# Sch_MCU.net
KiCad netlist of a schematic drawn in Altium Designer
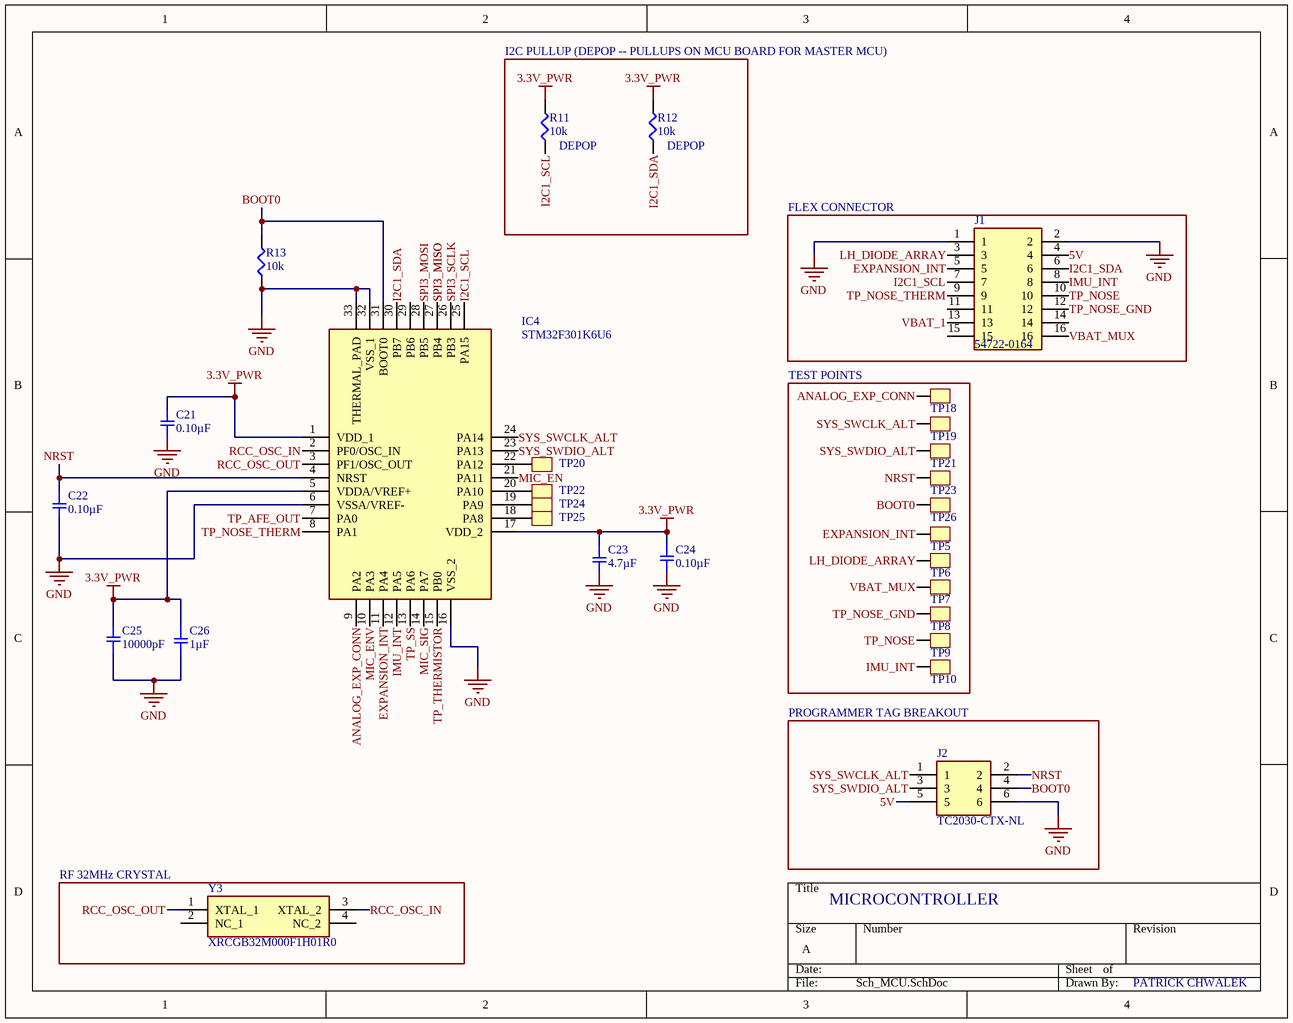
[diagram p0: Sch_MCU.SchDoc]

(export (version "E")
  (design (tool "Eeschema 10.0.6"))
  (components
    (comp (ref "C21")
      (value "0.10µF")
      (footprint "SMD-0402C")
      (description "CAP CER 0.1UF 16V X7R 0402")
      (fields
        (field (name "DIGI-KEY PART NUMBER") "490-4759-1-ND")
        (field (name "PART NUMBER") "GCM155R71C104KA55D")
      )
      (libsource (lib "capacitor_murata_0402") (part "GCM155R71C104KA55D"))
    )
    (comp (ref "C22")
      (value "0.10µF")
      (footprint "SMD-0402C")
      (description "CAP CER 0.1UF 16V X7R 0402")
      (fields
        (field (name "DIGI-KEY PART NUMBER") "490-4759-1-ND")
        (field (name "PART NUMBER") "GCM155R71C104KA55D")
      )
      (libsource (lib "capacitor_murata_0402") (part "GCM155R71C104KA55D"))
    )
    (comp (ref "C23")
      (value "4.7µF")
      (footprint "SMD-0402C")
      (description "CAP CER 4.7UF 4V X5R 0402")
      (fields
        (field (name "DIGI-KEY PART NUMBER") "490-13231-1-ND")
        (field (name "PART NUMBER") "GRM153R60G475ME15D")
      )
      (libsource (lib "capacitor_murata_0402") (part "GRM153R60G475ME15D"))
    )
    (comp (ref "C24")
      (value "0.10µF")
      (footprint "SMD-0402C")
      (description "CAP CER 0.1UF 16V X7R 0402")
      (fields
        (field (name "DIGI-KEY PART NUMBER") "490-4759-1-ND")
        (field (name "PART NUMBER") "GCM155R71C104KA55D")
      )
      (libsource (lib "capacitor_murata_0402") (part "GCM155R71C104KA55D"))
    )
    (comp (ref "C25")
      (value "10000pF")
      (footprint "SMD-0402C")
      (description "CAP CER 10000PF 50V X7R 0402")
      (fields
        (field (name "DIGI-KEY PART NUMBER") "490-4762-1-ND")
        (field (name "PART NUMBER") "GCM155R71H103KA55D")
      )
      (libsource (lib "capacitor_murata_0402") (part "GCM155R71H103KA55D"))
    )
    (comp (ref "C26")
      (value "1µF")
      (footprint "SMD-0402C")
      (description "CAP CER 1UF 10V X7S 0402")
      (fields
        (field (name "DIGI-KEY PART NUMBER") "490-13409-1-ND")
        (field (name "PART NUMBER") "GCM155C71A105KE38D")
      )
      (libsource (lib "capacitor_murata_0402") (part "GCM155C71A105KE38D"))
    )
    (comp (ref "IC4")
      (value "STM32F301K6U6")
      (footprint "SamacSys:QFN50P500X500X60-33N-D")
      (description "Integrated Circuit")
      (fields (field (name "MOUSER PART NUMBER") "511-STM32F301K6U6"))
      (libsource (lib "*") (part "STM32F301K6U6"))
    )
    (comp (ref "J1")
      (value "54722-0164")
      (footprint "SamacSys:54722-0164")
      (description "Connector")
      (fields (field (name "MOUSER PART NUMBER") "538-54722-0164") (field (name "RS PART NUMBER") "7206511"))
      (libsource (lib "*") (part "54722-0164"))
    )
    (comp (ref "J2")
      (value "TC2030-CTX-NL")
      (footprint "SamacSys:TC2030MCPNL10")
      (description "Connector")
      (libsource (lib "SamacSys") (part "TC2030-CTX-NL"))
    )
    (comp (ref "R11")
      (value "10k")
      (footprint "SMD-0402-RES")
      (description "RES SMD 10K OHM 5% 1/10W 0402")
      (fields (field (name "PART NUMBER") "ERJ-2GEJ103X") (field (name "DIGI-KEY PART NUMBER") "P10KJCT-ND"))
      (libsource (lib "Panasonic_ERJ_0402") (part "ERJ-2GEJ103X"))
    )
    (comp (ref "R12")
      (value "10k")
      (footprint "SMD-0402-RES")
      (description "RES SMD 10K OHM 5% 1/10W 0402")
      (fields (field (name "PART NUMBER") "ERJ-2GEJ103X") (field (name "DIGI-KEY PART NUMBER") "P10KJCT-ND"))
      (libsource (lib "Panasonic_ERJ_0402") (part "ERJ-2GEJ103X"))
    )
    (comp (ref "R13")
      (value "10k")
      (footprint "SMD-0402-RES")
      (description "RES SMD 10K OHM 5% 1/10W 0402")
      (fields (field (name "PART NUMBER") "ERJ-2GEJ103X") (field (name "DIGI-KEY PART NUMBER") "P10KJCT-ND"))
      (libsource (lib "Panasonic_ERJ_0402") (part "ERJ-2GEJ103X"))
    )
    (comp (ref "TP5")
      (value "TestPoint")
      (footprint "TestPoint_0.4mm")
      (libsource (lib "schematic_components") (part "TestPoint"))
    )
    (comp (ref "TP6")
      (value "TestPoint")
      (footprint "TestPoint_0.4mm")
      (libsource (lib "schematic_components") (part "TestPoint"))
    )
    (comp (ref "TP7")
      (value "TestPoint")
      (footprint "TestPoint_0.4mm")
      (libsource (lib "schematic_components") (part "TestPoint"))
    )
    (comp (ref "TP8")
      (value "TestPoint")
      (footprint "TestPoint_0.4mm")
      (libsource (lib "schematic_components") (part "TestPoint"))
    )
    (comp (ref "TP9")
      (value "TestPoint")
      (footprint "TestPoint_0.4mm")
      (libsource (lib "schematic_components") (part "TestPoint"))
    )
    (comp (ref "TP10")
      (value "TestPoint")
      (footprint "TestPoint_0.4mm")
      (libsource (lib "schematic_components") (part "TestPoint"))
    )
    (comp (ref "TP18")
      (value "TestPoint")
      (footprint "TestPoint_0.4mm")
      (libsource (lib "schematic_components") (part "TestPoint"))
    )
    (comp (ref "TP19")
      (value "TestPoint")
      (footprint "TestPoint_0.4mm")
      (libsource (lib "schematic_components") (part "TestPoint"))
    )
    (comp (ref "TP20")
      (value "TestPoint")
      (footprint "TESTPOINT_1MM_OVAL")
      (libsource (lib "schematic_components") (part "TestPoint"))
    )
    (comp (ref "TP21")
      (value "TestPoint")
      (footprint "TestPoint_0.4mm")
      (libsource (lib "schematic_components") (part "TestPoint"))
    )
    (comp (ref "TP22")
      (value "TestPoint")
      (footprint "TESTPOINT_1MM_OVAL")
      (libsource (lib "schematic_components") (part "TestPoint"))
    )
    (comp (ref "TP23")
      (value "TestPoint")
      (footprint "TestPoint_0.4mm")
      (libsource (lib "schematic_components") (part "TestPoint"))
    )
    (comp (ref "TP24")
      (value "TestPoint")
      (footprint "TESTPOINT_1MM_OVAL")
      (libsource (lib "schematic_components") (part "TestPoint"))
    )
    (comp (ref "TP25")
      (value "TestPoint")
      (footprint "TESTPOINT_1MM_OVAL")
      (libsource (lib "schematic_components") (part "TestPoint"))
    )
    (comp (ref "TP26")
      (value "TestPoint")
      (footprint "TestPoint_0.4mm")
      (libsource (lib "schematic_components") (part "TestPoint"))
    )
    (comp (ref "Y3")
      (value "XRCGB32M000F1H01R0")
      (footprint "SamacSys:XRCGB32M000F1H01R0")
      (description "Crystal or Oscillator")
      (fields (field (name "MOUSER PART NUMBER") "81-XRCGB32M000F1H01R"))
      (libsource (lib "SamacSys") (part "XRCGB32M000F1H01R0"))
    )
  )
  (nets
    (net (code "1") (name "/5V") (class "Default")
      (node (ref "J1") (pin "4") (pinfunction "4_4") (pintype "passive"))
      (node (ref "J2") (pin "5") (pinfunction "5_5") (pintype "passive"))
    )
    (net (code "2") (name "/ANALOG_EXP_CONN") (class "Default")
      (node (ref "IC4") (pin "9") (pinfunction "PA2_9") (pintype "passive"))
      (node (ref "TP18") (pin "1") (pinfunction "1_1") (pintype "passive"))
    )
    (net (code "3") (name "/BOOT0") (class "Default")
      (node (ref "IC4") (pin "31") (pinfunction "BOOT0_31") (pintype "passive"))
      (node (ref "J2") (pin "4") (pinfunction "4_4") (pintype "passive"))
      (node (ref "R13") (pin "2") (pinfunction "2_2") (pintype "passive"))
      (node (ref "TP26") (pin "1") (pinfunction "1_1") (pintype "passive"))
    )
    (net (code "4") (name "/EXPANSION_INT") (class "Default")
      (node (ref "IC4") (pin "11") (pinfunction "PA4_11") (pintype "passive"))
      (node (ref "J1") (pin "5") (pinfunction "5_5") (pintype "passive"))
      (node (ref "TP5") (pin "1") (pinfunction "1_1") (pintype "passive"))
    )
    (net (code "5") (name "/I2C1_SCL") (class "Default")
      (node (ref "IC4") (pin "25") (pinfunction "PA15_25") (pintype "passive"))
      (node (ref "J1") (pin "7") (pinfunction "7_7") (pintype "passive"))
      (node (ref "R11") (pin "1") (pinfunction "1_1") (pintype "passive"))
    )
    (net (code "6") (name "/I2C1_SDA") (class "Default")
      (node (ref "IC4") (pin "30") (pinfunction "PB7_30") (pintype "passive"))
      (node (ref "J1") (pin "6") (pinfunction "6_6") (pintype "passive"))
      (node (ref "R12") (pin "1") (pinfunction "1_1") (pintype "passive"))
    )
    (net (code "7") (name "/IMU_INT") (class "Default")
      (node (ref "IC4") (pin "12") (pinfunction "PA5_12") (pintype "passive"))
      (node (ref "J1") (pin "8") (pinfunction "8_8") (pintype "passive"))
      (node (ref "TP10") (pin "1") (pinfunction "1_1") (pintype "passive"))
    )
    (net (code "8") (name "/LH_DIODE_ARRAY") (class "Default")
      (node (ref "J1") (pin "3") (pinfunction "3_3") (pintype "passive"))
      (node (ref "TP6") (pin "1") (pinfunction "1_1") (pintype "passive"))
    )
    (net (code "9") (name "/MIC_EN") (class "Default")
      (node (ref "IC4") (pin "21") (pinfunction "PA11_21") (pintype "passive"))
    )
    (net (code "10") (name "/MIC_ENV") (class "Default")
      (node (ref "IC4") (pin "10") (pinfunction "PA3_10") (pintype "passive"))
    )
    (net (code "11") (name "/MIC_SIG") (class "Default")
      (node (ref "IC4") (pin "14") (pinfunction "PA7_14") (pintype "passive"))
    )
    (net (code "12") (name "/NRST") (class "Default")
      (node (ref "C22") (pin "1") (pinfunction "1_1") (pintype "passive"))
      (node (ref "IC4") (pin "4") (pinfunction "NRST_4") (pintype "passive"))
      (node (ref "J2") (pin "2") (pinfunction "2_2") (pintype "passive"))
      (node (ref "TP23") (pin "1") (pinfunction "1_1") (pintype "passive"))
    )
    (net (code "13") (name "/RCC_OSC_IN") (class "Default")
      (node (ref "IC4") (pin "2") (pinfunction "PF0/OSC_IN_2") (pintype "passive"))
      (node (ref "Y3") (pin "3") (pinfunction "XTAL_2_3") (pintype "passive"))
    )
    (net (code "14") (name "/RCC_OSC_OUT") (class "Default")
      (node (ref "IC4") (pin "3") (pinfunction "PF1/OSC_OUT_3") (pintype "passive"))
      (node (ref "Y3") (pin "1") (pinfunction "XTAL_1_1") (pintype "passive"))
    )
    (net (code "15") (name "/SPI3_MISO") (class "Default")
      (node (ref "IC4") (pin "27") (pinfunction "PB4_27") (pintype "passive"))
    )
    (net (code "16") (name "/SPI3_MOSI") (class "Default")
      (node (ref "IC4") (pin "28") (pinfunction "PB5_28") (pintype "passive"))
    )
    (net (code "17") (name "/SPI3_SCLK") (class "Default")
      (node (ref "IC4") (pin "26") (pinfunction "PB3_26") (pintype "passive"))
    )
    (net (code "18") (name "/SYS_SWCLK_ALT") (class "Default")
      (node (ref "IC4") (pin "24") (pinfunction "PA14_24") (pintype "passive"))
      (node (ref "J2") (pin "1") (pinfunction "1_1") (pintype "passive"))
      (node (ref "TP19") (pin "1") (pinfunction "1_1") (pintype "passive"))
    )
    (net (code "19") (name "/SYS_SWDIO_ALT") (class "Default")
      (node (ref "IC4") (pin "23") (pinfunction "PA13_23") (pintype "passive"))
      (node (ref "J2") (pin "3") (pinfunction "3_3") (pintype "passive"))
      (node (ref "TP21") (pin "1") (pinfunction "1_1") (pintype "passive"))
    )
    (net (code "20") (name "/TP_AFE_OUT") (class "Default")
      (node (ref "IC4") (pin "7") (pinfunction "PA0_7") (pintype "passive"))
    )
    (net (code "21") (name "/TP_NOSE") (class "Default")
      (node (ref "J1") (pin "10") (pinfunction "10_10") (pintype "passive"))
      (node (ref "TP9") (pin "1") (pinfunction "1_1") (pintype "passive"))
    )
    (net (code "22") (name "/TP_NOSE_GND") (class "Default")
      (node (ref "J1") (pin "12") (pinfunction "12_12") (pintype "passive"))
      (node (ref "TP8") (pin "1") (pinfunction "1_1") (pintype "passive"))
    )
    (net (code "23") (name "/TP_NOSE_THERM") (class "Default")
      (node (ref "IC4") (pin "8") (pinfunction "PA1_8") (pintype "passive"))
      (node (ref "J1") (pin "9") (pinfunction "9_9") (pintype "passive"))
    )
    (net (code "24") (name "/TP_SS") (class "Default")
      (node (ref "IC4") (pin "13") (pinfunction "PA6_13") (pintype "passive"))
    )
    (net (code "25") (name "/TP_THERMISTOR") (class "Default")
      (node (ref "IC4") (pin "15") (pinfunction "PB0_15") (pintype "passive"))
    )
    (net (code "26") (name "/VBAT_1") (class "Default")
      (node (ref "J1") (pin "13") (pinfunction "13_13") (pintype "passive"))
    )
    (net (code "27") (name "/VBAT_MUX") (class "Default")
      (node (ref "J1") (pin "16") (pinfunction "16_16") (pintype "passive"))
      (node (ref "TP7") (pin "1") (pinfunction "1_1") (pintype "passive"))
    )
    (net (code "28") (name "3.3V_PWR") (class "Default")
      (node (ref "C21") (pin "2") (pinfunction "2_2") (pintype "passive"))
      (node (ref "C23") (pin "1") (pinfunction "1_1") (pintype "passive"))
      (node (ref "C24") (pin "2") (pinfunction "2_2") (pintype "passive"))
      (node (ref "C25") (pin "2") (pinfunction "2_2") (pintype "passive"))
      (node (ref "C26") (pin "1") (pinfunction "1_1") (pintype "passive"))
      (node (ref "IC4") (pin "1") (pinfunction "VDD_1_1") (pintype "passive"))
      (node (ref "IC4") (pin "17") (pinfunction "VDD_2_17") (pintype "passive"))
      (node (ref "IC4") (pin "5") (pinfunction "VDDA/VREF+_5") (pintype "passive"))
      (node (ref "R11") (pin "2") (pinfunction "2_2") (pintype "passive"))
      (node (ref "R12") (pin "2") (pinfunction "2_2") (pintype "passive"))
    )
    (net (code "29") (name "GND") (class "Default")
      (node (ref "C21") (pin "1") (pinfunction "1_1") (pintype "passive"))
      (node (ref "C22") (pin "2") (pinfunction "2_2") (pintype "passive"))
      (node (ref "C23") (pin "2") (pinfunction "2_2") (pintype "passive"))
      (node (ref "C24") (pin "1") (pinfunction "1_1") (pintype "passive"))
      (node (ref "C25") (pin "1") (pinfunction "1_1") (pintype "passive"))
      (node (ref "C26") (pin "2") (pinfunction "2_2") (pintype "passive"))
      (node (ref "IC4") (pin "16") (pinfunction "VSS_2_16") (pintype "passive"))
      (node (ref "IC4") (pin "32") (pinfunction "VSS_1_32") (pintype "passive"))
      (node (ref "IC4") (pin "33") (pinfunction "THERMAL_PAD_33") (pintype "passive"))
      (node (ref "IC4") (pin "6") (pinfunction "VSSA/VREF-_6") (pintype "passive"))
      (node (ref "J1") (pin "1") (pinfunction "1_1") (pintype "passive"))
      (node (ref "J1") (pin "2") (pinfunction "2_2") (pintype "passive"))
      (node (ref "J2") (pin "6") (pinfunction "6_6") (pintype "passive"))
      (node (ref "R13") (pin "1") (pinfunction "1_1") (pintype "passive"))
    )
    (net (code "30") (name "Net-(IC4-PA8)") (class "Default")
      (node (ref "IC4") (pin "18") (pinfunction "PA8_18") (pintype "passive"))
      (node (ref "TP25") (pin "1") (pinfunction "1_1") (pintype "passive"))
    )
    (net (code "31") (name "Net-(IC4-PA9)") (class "Default")
      (node (ref "IC4") (pin "19") (pinfunction "PA9_19") (pintype "passive"))
      (node (ref "TP24") (pin "1") (pinfunction "1_1") (pintype "passive"))
    )
    (net (code "32") (name "Net-(IC4-PA10)") (class "Default")
      (node (ref "IC4") (pin "20") (pinfunction "PA10_20") (pintype "passive"))
      (node (ref "TP22") (pin "1") (pinfunction "1_1") (pintype "passive"))
    )
    (net (code "33") (name "Net-(IC4-PA12)") (class "Default")
      (node (ref "IC4") (pin "22") (pinfunction "PA12_22") (pintype "passive"))
      (node (ref "TP20") (pin "1") (pinfunction "1_1") (pintype "passive"))
    )
    (net (code "34") (name "unconnected-(IC4-PB6-Pad29)") (class "Default")
      (node (ref "IC4") (pin "29") (pinfunction "PB6_29") (pintype "passive"))
    )
    (net (code "35") (name "unconnected-(J1-Pad11)") (class "Default")
      (node (ref "J1") (pin "11") (pinfunction "11_11") (pintype "passive"))
    )
    (net (code "36") (name "unconnected-(J1-Pad14)") (class "Default")
      (node (ref "J1") (pin "14") (pinfunction "14_14") (pintype "passive"))
    )
    (net (code "37") (name "unconnected-(J1-Pad15)") (class "Default")
      (node (ref "J1") (pin "15") (pinfunction "15_15") (pintype "passive"))
    )
    (net (code "38") (name "unconnected-(Y3-NC_1-Pad2)") (class "Default")
      (node (ref "Y3") (pin "2") (pinfunction "NC_1_2") (pintype "passive"))
    )
    (net (code "39") (name "unconnected-(Y3-NC_2-Pad4)") (class "Default")
      (node (ref "Y3") (pin "4") (pinfunction "NC_2_4") (pintype "passive"))
    )
  )
)
